# Schieberegister_Tr_gerplatine.net
KiCad netlist of a schematic drawn in Altium Designer
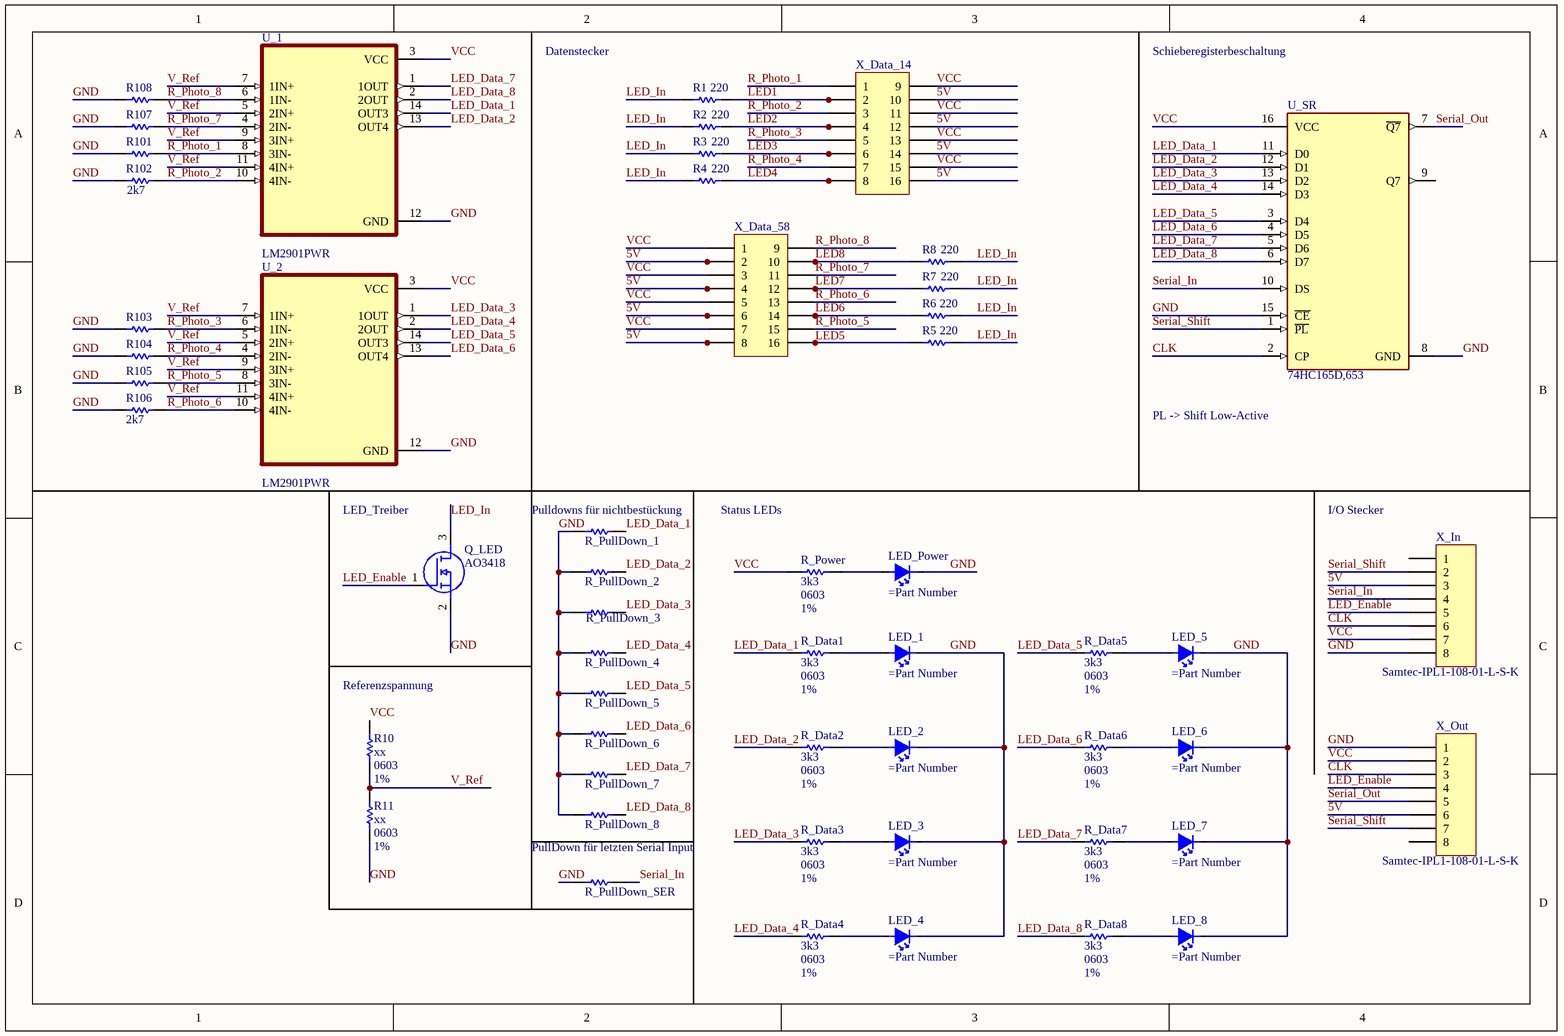
[diagram p0: Schieberegister_Trägerplatine.SchDoc]

(export (version "E")
  (design (tool "Eeschema 10.0.6"))
  (components
    (comp (ref "LED_1")
      (value "~")
      (footprint "150060XX75000")
      (fields (field (name "PART NUMBER") "150060*75000") (field (name "MANUFACTURER") "Würth"))
      (libsource (lib "FSE_Library_nora7") (part "LED_0603"))
    )
    (comp (ref "LED_2")
      (value "~")
      (footprint "150060XX75000")
      (fields (field (name "PART NUMBER") "150060*75000") (field (name "MANUFACTURER") "Würth"))
      (libsource (lib "FSE_Library_nora7") (part "LED_0603"))
    )
    (comp (ref "LED_3")
      (value "~")
      (footprint "150060XX75000")
      (fields (field (name "PART NUMBER") "150060*75000") (field (name "MANUFACTURER") "Würth"))
      (libsource (lib "FSE_Library_nora7") (part "LED_0603"))
    )
    (comp (ref "LED_4")
      (value "~")
      (footprint "150060XX75000")
      (fields (field (name "PART NUMBER") "150060*75000") (field (name "MANUFACTURER") "Würth"))
      (libsource (lib "FSE_Library_nora7") (part "LED_0603"))
    )
    (comp (ref "LED_5")
      (value "~")
      (footprint "150060XX75000")
      (fields (field (name "PART NUMBER") "150060*75000") (field (name "MANUFACTURER") "Würth"))
      (libsource (lib "FSE_Library_nora7") (part "LED_0603"))
    )
    (comp (ref "LED_6")
      (value "~")
      (footprint "150060XX75000")
      (fields (field (name "PART NUMBER") "150060*75000") (field (name "MANUFACTURER") "Würth"))
      (libsource (lib "FSE_Library_nora7") (part "LED_0603"))
    )
    (comp (ref "LED_7")
      (value "~")
      (footprint "150060XX75000")
      (fields (field (name "PART NUMBER") "150060*75000") (field (name "MANUFACTURER") "Würth"))
      (libsource (lib "FSE_Library_nora7") (part "LED_0603"))
    )
    (comp (ref "LED_8")
      (value "~")
      (footprint "150060XX75000")
      (fields (field (name "PART NUMBER") "150060*75000") (field (name "MANUFACTURER") "Würth"))
      (libsource (lib "FSE_Library_nora7") (part "LED_0603"))
    )
    (comp (ref "LED_Power")
      (value "~")
      (footprint "150060XX75000")
      (fields (field (name "PART NUMBER") "150060*75000") (field (name "MANUFACTURER") "Würth"))
      (libsource (lib "FSE_Library_nora7") (part "LED_0603"))
    )
    (comp (ref "Q_LED")
      (value "AO3418")
      (footprint "SOT95P280X125-3N")
      (description "MOSFET N-CH 30V 3.8A SOT23")
      (libsource (lib "AO3418") (part "AO3418"))
    )
    (comp (ref "R1")
      (value "220")
      (footprint "FSE_Library_nora7:0603_resistor_flat")
      (description "Resistor, 0603, 5% default, 0.1 W")
      (fields (field (name "PART NUMBER") "R___220"))
      (libsource (lib "FSE_Library_nora7") (part "R_0603"))
    )
    (comp (ref "R2")
      (value "220")
      (footprint "FSE_Library_nora7:0603_resistor_flat")
      (description "Resistor, 0603, 5% default, 0.1 W")
      (fields (field (name "PART NUMBER") "R___220"))
      (libsource (lib "FSE_Library_nora7") (part "R_0603"))
    )
    (comp (ref "R3")
      (value "220")
      (footprint "FSE_Library_nora7:0603_resistor_flat")
      (description "Resistor, 0603, 5% default, 0.1 W")
      (fields (field (name "PART NUMBER") "R___220"))
      (libsource (lib "FSE_Library_nora7") (part "R_0603"))
    )
    (comp (ref "R4")
      (value "220")
      (footprint "FSE_Library_nora7:0603_resistor_flat")
      (description "Resistor, 0603, 5% default, 0.1 W")
      (fields (field (name "PART NUMBER") "R___220"))
      (libsource (lib "FSE_Library_nora7") (part "R_0603"))
    )
    (comp (ref "R5")
      (value "220")
      (footprint "FSE_Library_nora7:0603_resistor_flat")
      (description "Resistor, 0603, 5% default, 0.1 W")
      (fields (field (name "PART NUMBER") "R___220"))
      (libsource (lib "FSE_Library_nora7") (part "R_0603"))
    )
    (comp (ref "R6")
      (value "220")
      (footprint "FSE_Library_nora7:0603_resistor_flat")
      (description "Resistor, 0603, 5% default, 0.1 W")
      (fields (field (name "PART NUMBER") "R___220"))
      (libsource (lib "FSE_Library_nora7") (part "R_0603"))
    )
    (comp (ref "R7")
      (value "220")
      (footprint "FSE_Library_nora7:0603_resistor_flat")
      (description "Resistor, 0603, 5% default, 0.1 W")
      (fields (field (name "PART NUMBER") "R___220"))
      (libsource (lib "FSE_Library_nora7") (part "R_0603"))
    )
    (comp (ref "R8")
      (value "220")
      (footprint "FSE_Library_nora7:0603_resistor_flat")
      (description "Resistor, 0603, 5% default, 0.1 W")
      (fields (field (name "PART NUMBER") "R___220"))
      (libsource (lib "FSE_Library_nora7") (part "R_0603"))
    )
    (comp (ref "R10")
      (value "xx")
      (footprint "FSE_Library_nora7:0603_resistor_flat")
      (description "Resistor, 0603, 5% default, 0.1 W")
      (fields
        (field (name "PART NUMBER") "R_0603_1%_xx")
        (field (name "CASE_EIA") "0603")
        (field (name "TOLERANCE") "1%")
      )
      (libsource (lib "FSE_Library_nora7") (part "R_0603"))
    )
    (comp (ref "R11")
      (value "xx")
      (footprint "FSE_Library_nora7:0603_resistor_flat")
      (description "Resistor, 0603, 5% default, 0.1 W")
      (fields
        (field (name "PART NUMBER") "R_0603_1%_xx")
        (field (name "CASE_EIA") "0603")
        (field (name "TOLERANCE") "1%")
      )
      (libsource (lib "FSE_Library_nora7") (part "R_0603"))
    )
    (comp (ref "R101")
      (value "~")
      (footprint "FSE_Library_nora7:0603_resistor_flat")
      (description "Resistor, 0603, 5% default, 0.1 W")
      (fields (field (name "PART NUMBER") "R___"))
      (libsource (lib "FSE_Library_nora7") (part "R_0603"))
    )
    (comp (ref "R102")
      (value "2k7")
      (footprint "FSE_Library_nora7:0603_resistor_flat")
      (description "Resistor, 0603, 5% default, 0.1 W")
      (fields (field (name "PART NUMBER") "R___"))
      (libsource (lib "FSE_Library_nora7") (part "R_0603"))
    )
    (comp (ref "R103")
      (value "~")
      (footprint "FSE_Library_nora7:0603_resistor_flat")
      (description "Resistor, 0603, 5% default, 0.1 W")
      (fields (field (name "PART NUMBER") "R___"))
      (libsource (lib "FSE_Library_nora7") (part "R_0603"))
    )
    (comp (ref "R104")
      (value "~")
      (footprint "FSE_Library_nora7:0603_resistor_flat")
      (description "Resistor, 0603, 5% default, 0.1 W")
      (fields (field (name "PART NUMBER") "R___"))
      (libsource (lib "FSE_Library_nora7") (part "R_0603"))
    )
    (comp (ref "R105")
      (value "~")
      (footprint "FSE_Library_nora7:0603_resistor_flat")
      (description "Resistor, 0603, 5% default, 0.1 W")
      (fields (field (name "PART NUMBER") "R___"))
      (libsource (lib "FSE_Library_nora7") (part "R_0603"))
    )
    (comp (ref "R106")
      (value "2k7")
      (footprint "FSE_Library_nora7:0603_resistor_flat")
      (description "Resistor, 0603, 5% default, 0.1 W")
      (fields (field (name "PART NUMBER") "R___"))
      (libsource (lib "FSE_Library_nora7") (part "R_0603"))
    )
    (comp (ref "R107")
      (value "~")
      (footprint "FSE_Library_nora7:0603_resistor_flat")
      (description "Resistor, 0603, 5% default, 0.1 W")
      (fields (field (name "PART NUMBER") "R___"))
      (libsource (lib "FSE_Library_nora7") (part "R_0603"))
    )
    (comp (ref "R108")
      (value "~")
      (footprint "FSE_Library_nora7:0603_resistor_flat")
      (description "Resistor, 0603, 5% default, 0.1 W")
      (fields (field (name "PART NUMBER") "R___"))
      (libsource (lib "FSE_Library_nora7") (part "R_0603"))
    )
    (comp (ref "R_Data1")
      (value "3k3")
      (footprint "FSE_Library_nora7:0603_resistor_flat")
      (description "Resistor, 0603, 5% default, 0.1 W")
      (fields
        (field (name "PART NUMBER") "R_0603_1%_3k3")
        (field (name "CASE_EIA") "0603")
        (field (name "TOLERANCE") "1%")
      )
      (libsource (lib "FSE_Library_nora7") (part "R_0603"))
    )
    (comp (ref "R_Data2")
      (value "3k3")
      (footprint "FSE_Library_nora7:0603_resistor_flat")
      (description "Resistor, 0603, 5% default, 0.1 W")
      (fields
        (field (name "PART NUMBER") "R_0603_1%_3k3")
        (field (name "CASE_EIA") "0603")
        (field (name "TOLERANCE") "1%")
      )
      (libsource (lib "FSE_Library_nora7") (part "R_0603"))
    )
    (comp (ref "R_Data3")
      (value "3k3")
      (footprint "FSE_Library_nora7:0603_resistor_flat")
      (description "Resistor, 0603, 5% default, 0.1 W")
      (fields
        (field (name "PART NUMBER") "R_0603_1%_3k3")
        (field (name "CASE_EIA") "0603")
        (field (name "TOLERANCE") "1%")
      )
      (libsource (lib "FSE_Library_nora7") (part "R_0603"))
    )
    (comp (ref "R_Data4")
      (value "3k3")
      (footprint "FSE_Library_nora7:0603_resistor_flat")
      (description "Resistor, 0603, 5% default, 0.1 W")
      (fields
        (field (name "PART NUMBER") "R_0603_1%_3k3")
        (field (name "CASE_EIA") "0603")
        (field (name "TOLERANCE") "1%")
      )
      (libsource (lib "FSE_Library_nora7") (part "R_0603"))
    )
    (comp (ref "R_Data5")
      (value "3k3")
      (footprint "FSE_Library_nora7:0603_resistor_flat")
      (description "Resistor, 0603, 5% default, 0.1 W")
      (fields
        (field (name "PART NUMBER") "R_0603_1%_3k3")
        (field (name "CASE_EIA") "0603")
        (field (name "TOLERANCE") "1%")
      )
      (libsource (lib "FSE_Library_nora7") (part "R_0603"))
    )
    (comp (ref "R_Data6")
      (value "3k3")
      (footprint "FSE_Library_nora7:0603_resistor_flat")
      (description "Resistor, 0603, 5% default, 0.1 W")
      (fields
        (field (name "PART NUMBER") "R_0603_1%_3k3")
        (field (name "CASE_EIA") "0603")
        (field (name "TOLERANCE") "1%")
      )
      (libsource (lib "FSE_Library_nora7") (part "R_0603"))
    )
    (comp (ref "R_Data7")
      (value "3k3")
      (footprint "FSE_Library_nora7:0603_resistor_flat")
      (description "Resistor, 0603, 5% default, 0.1 W")
      (fields
        (field (name "PART NUMBER") "R_0603_1%_3k3")
        (field (name "CASE_EIA") "0603")
        (field (name "TOLERANCE") "1%")
      )
      (libsource (lib "FSE_Library_nora7") (part "R_0603"))
    )
    (comp (ref "R_Data8")
      (value "3k3")
      (footprint "FSE_Library_nora7:0603_resistor_flat")
      (description "Resistor, 0603, 5% default, 0.1 W")
      (fields
        (field (name "PART NUMBER") "R_0603_1%_3k3")
        (field (name "CASE_EIA") "0603")
        (field (name "TOLERANCE") "1%")
      )
      (libsource (lib "FSE_Library_nora7") (part "R_0603"))
    )
    (comp (ref "R_Power")
      (value "3k3")
      (footprint "FSE_Library_nora7:0603_resistor_flat")
      (description "Resistor, 0603, 5% default, 0.1 W")
      (fields
        (field (name "PART NUMBER") "R_0603_1%_3k3")
        (field (name "CASE_EIA") "0603")
        (field (name "TOLERANCE") "1%")
      )
      (libsource (lib "FSE_Library_nora7") (part "R_0603"))
    )
    (comp (ref "R_PullDown_1")
      (value "~")
      (footprint "FSE_Library_nora7:0603_resistor_flat")
      (description "Resistor, 0603, 5% default, 0.1 W")
      (fields (field (name "PART NUMBER") "R___"))
      (libsource (lib "FSE_Library_nora7") (part "R_0603"))
    )
    (comp (ref "R_PullDown_2")
      (value "~")
      (footprint "FSE_Library_nora7:0603_resistor_flat")
      (description "Resistor, 0603, 5% default, 0.1 W")
      (fields (field (name "PART NUMBER") "R___"))
      (libsource (lib "FSE_Library_nora7") (part "R_0603"))
    )
    (comp (ref "R_PullDown_3")
      (value "~")
      (footprint "FSE_Library_nora7:0603_resistor_flat")
      (description "Resistor, 0603, 5% default, 0.1 W")
      (fields (field (name "PART NUMBER") "R___"))
      (libsource (lib "FSE_Library_nora7") (part "R_0603"))
    )
    (comp (ref "R_PullDown_4")
      (value "~")
      (footprint "FSE_Library_nora7:0603_resistor_flat")
      (description "Resistor, 0603, 5% default, 0.1 W")
      (fields (field (name "PART NUMBER") "R___"))
      (libsource (lib "FSE_Library_nora7") (part "R_0603"))
    )
    (comp (ref "R_PullDown_5")
      (value "~")
      (footprint "FSE_Library_nora7:0603_resistor_flat")
      (description "Resistor, 0603, 5% default, 0.1 W")
      (fields (field (name "PART NUMBER") "R___"))
      (libsource (lib "FSE_Library_nora7") (part "R_0603"))
    )
    (comp (ref "R_PullDown_6")
      (value "~")
      (footprint "FSE_Library_nora7:0603_resistor_flat")
      (description "Resistor, 0603, 5% default, 0.1 W")
      (fields (field (name "PART NUMBER") "R___"))
      (libsource (lib "FSE_Library_nora7") (part "R_0603"))
    )
    (comp (ref "R_PullDown_7")
      (value "~")
      (footprint "FSE_Library_nora7:0603_resistor_flat")
      (description "Resistor, 0603, 5% default, 0.1 W")
      (fields (field (name "PART NUMBER") "R___"))
      (libsource (lib "FSE_Library_nora7") (part "R_0603"))
    )
    (comp (ref "R_PullDown_8")
      (value "~")
      (footprint "FSE_Library_nora7:0603_resistor_flat")
      (description "Resistor, 0603, 5% default, 0.1 W")
      (fields (field (name "PART NUMBER") "R___"))
      (libsource (lib "FSE_Library_nora7") (part "R_0603"))
    )
    (comp (ref "R_PullDown_SER")
      (value "~")
      (footprint "FSE_Library_nora7:0603_resistor_flat")
      (description "Resistor, 0603, 5% default, 0.1 W")
      (fields (field (name "PART NUMBER") "R___"))
      (libsource (lib "FSE_Library_nora7") (part "R_0603"))
    )
    (comp (ref "U_1")
      (value "LM2901PWR")
      (footprint "SOP65P640X120-14N")
      (description "Quad differential comparator, automotive grade 14-TSSOP -40 to 125")
      (fields (field (name "MF") "Texas"))
      (libsource (lib "LM2901PWR") (part "LM2901PWR"))
    )
    (comp (ref "U_2")
      (value "LM2901PWR")
      (footprint "SOP65P640X120-14N")
      (description "Quad differential comparator, automotive grade 14-TSSOP -40 to 125")
      (fields (field (name "MF") "Texas"))
      (libsource (lib "LM2901PWR") (part "LM2901PWR"))
    )
    (comp (ref "U_SR")
      (value "74HC165D,653")
      (footprint "FP-SOT109-1-MFG")
      (description "IC SHIFT REGST 8BIT PI-SO 16SOIC")
      (fields
        (field (name "MANUFACTURER") "Nexperia")
        (field (name "OCTOPART") "https://octopart.com/74hc165d%2C653-nexperia-78737091")
      )
      (libsource (lib "Altium Content Vault") (part "62206be407dde36a55674a9f8997e2d"))
    )
    (comp (ref "X_Data_14")
      (value "Samtec-IPL1-108-01-L-D-K")
      (footprint "Samtec-IPL1-108-01-L-D-K")
      (description "Header, 8-Pin, Dual row")
      (fields (field (name "PUBLISHER") "Altium Limited"))
      (libsource (lib "FSE_Library_connector") (part "Samtec-IPL1-108-01-L-D-K"))
    )
    (comp (ref "X_Data_58")
      (value "Samtec-IPL1-108-01-L-D-K")
      (footprint "Samtec-IPL1-108-01-L-D-K")
      (description "Header, 8-Pin, Dual row")
      (fields (field (name "PUBLISHER") "Altium Limited"))
      (libsource (lib "FSE_Library_connector") (part "Samtec-IPL1-108-01-L-D-K"))
    )
    (comp (ref "X_In")
      (value "Samtec-IPL1-108-01-L-S-K")
      (footprint "Samtec-IPL1-108-01-L-S-K")
      (description "Header, 8-Pin")
      (fields (field (name "PUBLISHER") "Altium Limited"))
      (libsource (lib "FSE_Library_connector") (part "IPL1-108-01-L-S-K"))
    )
    (comp (ref "X_Out")
      (value "Samtec-IPL1-108-01-L-S-K")
      (footprint "Samtec-IPL1-108-01-L-S-K")
      (description "Header, 8-Pin")
      (fields (field (name "PUBLISHER") "Altium Limited"))
      (libsource (lib "FSE_Library_connector") (part "IPL1-108-01-L-S-K"))
    )
  )
  (nets
    (net (code "1") (name "/5V") (class "Default")
      (node (ref "X_Data_14") (pin "10") (pinfunction "10_10") (pintype "passive"))
      (node (ref "X_Data_14") (pin "12") (pinfunction "12_12") (pintype "passive"))
      (node (ref "X_Data_14") (pin "14") (pinfunction "14_14") (pintype "passive"))
      (node (ref "X_Data_14") (pin "16") (pinfunction "16_16") (pintype "passive"))
      (node (ref "X_Data_58") (pin "2") (pinfunction "2_2") (pintype "passive"))
      (node (ref "X_Data_58") (pin "4") (pinfunction "4_4") (pintype "passive"))
      (node (ref "X_Data_58") (pin "6") (pinfunction "6_6") (pintype "passive"))
      (node (ref "X_Data_58") (pin "8") (pinfunction "8_8") (pintype "passive"))
      (node (ref "X_In") (pin "3") (pinfunction "3_3") (pintype "passive"))
      (node (ref "X_Out") (pin "6") (pinfunction "6_6") (pintype "passive"))
    )
    (net (code "2") (name "/CLK") (class "Default")
      (node (ref "U_SR") (pin "2") (pinfunction "CP_2") (pintype "input"))
      (node (ref "X_In") (pin "6") (pinfunction "6_6") (pintype "passive"))
      (node (ref "X_Out") (pin "3") (pinfunction "3_3") (pintype "passive"))
    )
    (net (code "3") (name "/GND") (class "Default")
      (node (ref "LED_1") (pin "1") (pinfunction "Cathode_1") (pintype "passive"))
      (node (ref "LED_2") (pin "1") (pinfunction "Cathode_1") (pintype "passive"))
      (node (ref "LED_3") (pin "1") (pinfunction "Cathode_1") (pintype "passive"))
      (node (ref "LED_4") (pin "1") (pinfunction "Cathode_1") (pintype "passive"))
      (node (ref "LED_5") (pin "1") (pinfunction "Cathode_1") (pintype "passive"))
      (node (ref "LED_6") (pin "1") (pinfunction "Cathode_1") (pintype "passive"))
      (node (ref "LED_7") (pin "1") (pinfunction "Cathode_1") (pintype "passive"))
      (node (ref "LED_8") (pin "1") (pinfunction "Cathode_1") (pintype "passive"))
      (node (ref "LED_Power") (pin "1") (pinfunction "Cathode_1") (pintype "passive"))
      (node (ref "Q_LED") (pin "2") (pinfunction "S_2") (pintype "passive"))
      (node (ref "R101") (pin "1") (pinfunction "1_1") (pintype "passive"))
      (node (ref "R102") (pin "1") (pinfunction "1_1") (pintype "passive"))
      (node (ref "R103") (pin "1") (pinfunction "1_1") (pintype "passive"))
      (node (ref "R104") (pin "1") (pinfunction "1_1") (pintype "passive"))
      (node (ref "R105") (pin "1") (pinfunction "1_1") (pintype "passive"))
      (node (ref "R106") (pin "1") (pinfunction "1_1") (pintype "passive"))
      (node (ref "R107") (pin "1") (pinfunction "1_1") (pintype "passive"))
      (node (ref "R108") (pin "1") (pinfunction "1_1") (pintype "passive"))
      (node (ref "R11") (pin "1") (pinfunction "1_1") (pintype "passive"))
      (node (ref "R_PullDown_1") (pin "1") (pinfunction "1_1") (pintype "passive"))
      (node (ref "R_PullDown_2") (pin "1") (pinfunction "1_1") (pintype "passive"))
      (node (ref "R_PullDown_3") (pin "1") (pinfunction "1_1") (pintype "passive"))
      (node (ref "R_PullDown_4") (pin "1") (pinfunction "1_1") (pintype "passive"))
      (node (ref "R_PullDown_5") (pin "1") (pinfunction "1_1") (pintype "passive"))
      (node (ref "R_PullDown_6") (pin "1") (pinfunction "1_1") (pintype "passive"))
      (node (ref "R_PullDown_7") (pin "1") (pinfunction "1_1") (pintype "passive"))
      (node (ref "R_PullDown_8") (pin "1") (pinfunction "1_1") (pintype "passive"))
      (node (ref "R_PullDown_SER") (pin "1") (pinfunction "1_1") (pintype "passive"))
      (node (ref "U_1") (pin "12") (pinfunction "GND_12") (pintype "power_in"))
      (node (ref "U_2") (pin "12") (pinfunction "GND_12") (pintype "power_in"))
      (node (ref "U_SR") (pin "15") (pinfunction "~{CE}_15") (pintype "input"))
      (node (ref "U_SR") (pin "8") (pinfunction "GND_8") (pintype "power_in"))
      (node (ref "X_In") (pin "8") (pinfunction "8_8") (pintype "passive"))
      (node (ref "X_Out") (pin "1") (pinfunction "1_1") (pintype "passive"))
    )
    (net (code "4") (name "/LED1") (class "Default")
      (node (ref "R1") (pin "1") (pinfunction "1_1") (pintype "passive"))
      (node (ref "X_Data_14") (pin "2") (pinfunction "2_2") (pintype "passive"))
    )
    (net (code "5") (name "/LED2") (class "Default")
      (node (ref "R2") (pin "1") (pinfunction "1_1") (pintype "passive"))
      (node (ref "X_Data_14") (pin "4") (pinfunction "4_4") (pintype "passive"))
    )
    (net (code "6") (name "/LED3") (class "Default")
      (node (ref "R3") (pin "1") (pinfunction "1_1") (pintype "passive"))
      (node (ref "X_Data_14") (pin "6") (pinfunction "6_6") (pintype "passive"))
    )
    (net (code "7") (name "/LED4") (class "Default")
      (node (ref "R4") (pin "1") (pinfunction "1_1") (pintype "passive"))
      (node (ref "X_Data_14") (pin "8") (pinfunction "8_8") (pintype "passive"))
    )
    (net (code "8") (name "/LED5") (class "Default")
      (node (ref "R5") (pin "1") (pinfunction "1_1") (pintype "passive"))
      (node (ref "X_Data_58") (pin "16") (pinfunction "16_16") (pintype "passive"))
    )
    (net (code "9") (name "/LED6") (class "Default")
      (node (ref "R6") (pin "1") (pinfunction "1_1") (pintype "passive"))
      (node (ref "X_Data_58") (pin "14") (pinfunction "14_14") (pintype "passive"))
    )
    (net (code "10") (name "/LED7") (class "Default")
      (node (ref "R7") (pin "1") (pinfunction "1_1") (pintype "passive"))
      (node (ref "X_Data_58") (pin "12") (pinfunction "12_12") (pintype "passive"))
    )
    (net (code "11") (name "/LED8") (class "Default")
      (node (ref "R8") (pin "1") (pinfunction "1_1") (pintype "passive"))
      (node (ref "X_Data_58") (pin "10") (pinfunction "10_10") (pintype "passive"))
    )
    (net (code "12") (name "/LED_Data_1") (class "Default")
      (node (ref "R_Data1") (pin "2") (pinfunction "2_2") (pintype "passive"))
      (node (ref "R_PullDown_1") (pin "2") (pinfunction "2_2") (pintype "passive"))
      (node (ref "U_1") (pin "14") (pinfunction "OUT3_14") (pintype "output"))
      (node (ref "U_SR") (pin "11") (pinfunction "D0_11") (pintype "input"))
    )
    (net (code "13") (name "/LED_Data_2") (class "Default")
      (node (ref "R_Data2") (pin "2") (pinfunction "2_2") (pintype "passive"))
      (node (ref "R_PullDown_2") (pin "2") (pinfunction "2_2") (pintype "passive"))
      (node (ref "U_1") (pin "13") (pinfunction "OUT4_13") (pintype "output"))
      (node (ref "U_SR") (pin "12") (pinfunction "D1_12") (pintype "input"))
    )
    (net (code "14") (name "/LED_Data_3") (class "Default")
      (node (ref "R_Data3") (pin "2") (pinfunction "2_2") (pintype "passive"))
      (node (ref "R_PullDown_3") (pin "2") (pinfunction "2_2") (pintype "passive"))
      (node (ref "U_2") (pin "1") (pinfunction "1OUT_1") (pintype "output"))
      (node (ref "U_SR") (pin "13") (pinfunction "D2_13") (pintype "input"))
    )
    (net (code "15") (name "/LED_Data_4") (class "Default")
      (node (ref "R_Data4") (pin "2") (pinfunction "2_2") (pintype "passive"))
      (node (ref "R_PullDown_4") (pin "2") (pinfunction "2_2") (pintype "passive"))
      (node (ref "U_2") (pin "2") (pinfunction "2OUT_2") (pintype "output"))
      (node (ref "U_SR") (pin "14") (pinfunction "D3_14") (pintype "input"))
    )
    (net (code "16") (name "/LED_Data_5") (class "Default")
      (node (ref "R_Data5") (pin "2") (pinfunction "2_2") (pintype "passive"))
      (node (ref "R_PullDown_5") (pin "2") (pinfunction "2_2") (pintype "passive"))
      (node (ref "U_2") (pin "14") (pinfunction "OUT3_14") (pintype "output"))
      (node (ref "U_SR") (pin "3") (pinfunction "D4_3") (pintype "input"))
    )
    (net (code "17") (name "/LED_Data_6") (class "Default")
      (node (ref "R_Data6") (pin "2") (pinfunction "2_2") (pintype "passive"))
      (node (ref "R_PullDown_6") (pin "2") (pinfunction "2_2") (pintype "passive"))
      (node (ref "U_2") (pin "13") (pinfunction "OUT4_13") (pintype "output"))
      (node (ref "U_SR") (pin "4") (pinfunction "D5_4") (pintype "input"))
    )
    (net (code "18") (name "/LED_Data_7") (class "Default")
      (node (ref "R_Data7") (pin "2") (pinfunction "2_2") (pintype "passive"))
      (node (ref "R_PullDown_7") (pin "2") (pinfunction "2_2") (pintype "passive"))
      (node (ref "U_1") (pin "1") (pinfunction "1OUT_1") (pintype "output"))
      (node (ref "U_SR") (pin "5") (pinfunction "D6_5") (pintype "input"))
    )
    (net (code "19") (name "/LED_Data_8") (class "Default")
      (node (ref "R_Data8") (pin "2") (pinfunction "2_2") (pintype "passive"))
      (node (ref "R_PullDown_8") (pin "2") (pinfunction "2_2") (pintype "passive"))
      (node (ref "U_1") (pin "2") (pinfunction "2OUT_2") (pintype "output"))
      (node (ref "U_SR") (pin "6") (pinfunction "D7_6") (pintype "input"))
    )
    (net (code "20") (name "/LED_Enable") (class "Default")
      (node (ref "Q_LED") (pin "1") (pinfunction "G_1") (pintype "passive"))
      (node (ref "X_In") (pin "5") (pinfunction "5_5") (pintype "passive"))
      (node (ref "X_Out") (pin "4") (pinfunction "4_4") (pintype "passive"))
    )
    (net (code "21") (name "/LED_In") (class "Default")
      (node (ref "Q_LED") (pin "3") (pinfunction "D_3") (pintype "passive"))
      (node (ref "R1") (pin "2") (pinfunction "2_2") (pintype "passive"))
      (node (ref "R2") (pin "2") (pinfunction "2_2") (pintype "passive"))
      (node (ref "R3") (pin "2") (pinfunction "2_2") (pintype "passive"))
      (node (ref "R4") (pin "2") (pinfunction "2_2") (pintype "passive"))
      (node (ref "R5") (pin "2") (pinfunction "2_2") (pintype "passive"))
      (node (ref "R6") (pin "2") (pinfunction "2_2") (pintype "passive"))
      (node (ref "R7") (pin "2") (pinfunction "2_2") (pintype "passive"))
      (node (ref "R8") (pin "2") (pinfunction "2_2") (pintype "passive"))
    )
    (net (code "22") (name "/R_Photo_1") (class "Default")
      (node (ref "R101") (pin "2") (pinfunction "2_2") (pintype "passive"))
      (node (ref "U_1") (pin "8") (pinfunction "3IN-_8") (pintype "input"))
      (node (ref "X_Data_14") (pin "1") (pinfunction "1_1") (pintype "passive"))
    )
    (net (code "23") (name "/R_Photo_2") (class "Default")
      (node (ref "R102") (pin "2") (pinfunction "2_2") (pintype "passive"))
      (node (ref "U_1") (pin "10") (pinfunction "4IN-_10") (pintype "input"))
      (node (ref "X_Data_14") (pin "3") (pinfunction "3_3") (pintype "passive"))
    )
    (net (code "24") (name "/R_Photo_3") (class "Default")
      (node (ref "R103") (pin "2") (pinfunction "2_2") (pintype "passive"))
      (node (ref "U_2") (pin "6") (pinfunction "1IN-_6") (pintype "input"))
      (node (ref "X_Data_14") (pin "5") (pinfunction "5_5") (pintype "passive"))
    )
    (net (code "25") (name "/R_Photo_4") (class "Default")
      (node (ref "R104") (pin "2") (pinfunction "2_2") (pintype "passive"))
      (node (ref "U_2") (pin "4") (pinfunction "2IN-_4") (pintype "input"))
      (node (ref "X_Data_14") (pin "7") (pinfunction "7_7") (pintype "passive"))
    )
    (net (code "26") (name "/R_Photo_5") (class "Default")
      (node (ref "R105") (pin "2") (pinfunction "2_2") (pintype "passive"))
      (node (ref "U_2") (pin "8") (pinfunction "3IN-_8") (pintype "input"))
      (node (ref "X_Data_58") (pin "15") (pinfunction "15_15") (pintype "passive"))
    )
    (net (code "27") (name "/R_Photo_6") (class "Default")
      (node (ref "R106") (pin "2") (pinfunction "2_2") (pintype "passive"))
      (node (ref "U_2") (pin "10") (pinfunction "4IN-_10") (pintype "input"))
      (node (ref "X_Data_58") (pin "13") (pinfunction "13_13") (pintype "passive"))
    )
    (net (code "28") (name "/R_Photo_7") (class "Default")
      (node (ref "R107") (pin "2") (pinfunction "2_2") (pintype "passive"))
      (node (ref "U_1") (pin "4") (pinfunction "2IN-_4") (pintype "input"))
      (node (ref "X_Data_58") (pin "11") (pinfunction "11_11") (pintype "passive"))
    )
    (net (code "29") (name "/R_Photo_8") (class "Default")
      (node (ref "R108") (pin "2") (pinfunction "2_2") (pintype "passive"))
      (node (ref "U_1") (pin "6") (pinfunction "1IN-_6") (pintype "input"))
      (node (ref "X_Data_58") (pin "9") (pinfunction "9_9") (pintype "passive"))
    )
    (net (code "30") (name "/Serial_In") (class "Default")
      (node (ref "R_PullDown_SER") (pin "2") (pinfunction "2_2") (pintype "passive"))
      (node (ref "U_SR") (pin "10") (pinfunction "DS_10") (pintype "input"))
      (node (ref "X_In") (pin "4") (pinfunction "4_4") (pintype "passive"))
    )
    (net (code "31") (name "/Serial_Out") (class "Default")
      (node (ref "U_SR") (pin "7") (pinfunction "~{Q7}_7") (pintype "output"))
      (node (ref "X_Out") (pin "5") (pinfunction "5_5") (pintype "passive"))
    )
    (net (code "32") (name "/Serial_Shift") (class "Default")
      (node (ref "U_SR") (pin "1") (pinfunction "~{PL}_1") (pintype "input"))
      (node (ref "X_In") (pin "2") (pinfunction "2_2") (pintype "passive"))
      (node (ref "X_Out") (pin "7") (pinfunction "7_7") (pintype "passive"))
    )
    (net (code "33") (name "/VCC") (class "Default")
      (node (ref "R10") (pin "2") (pinfunction "2_2") (pintype "passive"))
      (node (ref "R_Power") (pin "2") (pinfunction "2_2") (pintype "passive"))
      (node (ref "U_1") (pin "3") (pinfunction "VCC_3") (pintype "power_in"))
      (node (ref "U_2") (pin "3") (pinfunction "VCC_3") (pintype "power_in"))
      (node (ref "U_SR") (pin "16") (pinfunction "VCC_16") (pintype "power_in"))
      (node (ref "X_Data_14") (pin "11") (pinfunction "11_11") (pintype "passive"))
      (node (ref "X_Data_14") (pin "13") (pinfunction "13_13") (pintype "passive"))
      (node (ref "X_Data_14") (pin "15") (pinfunction "15_15") (pintype "passive"))
      (node (ref "X_Data_14") (pin "9") (pinfunction "9_9") (pintype "passive"))
      (node (ref "X_Data_58") (pin "1") (pinfunction "1_1") (pintype "passive"))
      (node (ref "X_Data_58") (pin "3") (pinfunction "3_3") (pintype "passive"))
      (node (ref "X_Data_58") (pin "5") (pinfunction "5_5") (pintype "passive"))
      (node (ref "X_Data_58") (pin "7") (pinfunction "7_7") (pintype "passive"))
      (node (ref "X_In") (pin "7") (pinfunction "7_7") (pintype "passive"))
      (node (ref "X_Out") (pin "2") (pinfunction "2_2") (pintype "passive"))
    )
    (net (code "34") (name "/V_Ref") (class "Default")
      (node (ref "R10") (pin "1") (pinfunction "1_1") (pintype "passive"))
      (node (ref "R11") (pin "2") (pinfunction "2_2") (pintype "passive"))
      (node (ref "U_1") (pin "11") (pinfunction "4IN+_11") (pintype "input"))
      (node (ref "U_1") (pin "5") (pinfunction "2IN+_5") (pintype "input"))
      (node (ref "U_1") (pin "7") (pinfunction "1IN+_7") (pintype "input"))
      (node (ref "U_1") (pin "9") (pinfunction "3IN+_9") (pintype "input"))
      (node (ref "U_2") (pin "11") (pinfunction "4IN+_11") (pintype "input"))
      (node (ref "U_2") (pin "5") (pinfunction "2IN+_5") (pintype "input"))
      (node (ref "U_2") (pin "7") (pinfunction "1IN+_7") (pintype "input"))
      (node (ref "U_2") (pin "9") (pinfunction "3IN+_9") (pintype "input"))
    )
    (net (code "35") (name "Net-(LED_1-Anode)") (class "Default")
      (node (ref "LED_1") (pin "2") (pinfunction "Anode_2") (pintype "passive"))
      (node (ref "R_Data1") (pin "1") (pinfunction "1_1") (pintype "passive"))
    )
    (net (code "36") (name "Net-(LED_2-Anode)") (class "Default")
      (node (ref "LED_2") (pin "2") (pinfunction "Anode_2") (pintype "passive"))
      (node (ref "R_Data2") (pin "1") (pinfunction "1_1") (pintype "passive"))
    )
    (net (code "37") (name "Net-(LED_3-Anode)") (class "Default")
      (node (ref "LED_3") (pin "2") (pinfunction "Anode_2") (pintype "passive"))
      (node (ref "R_Data3") (pin "1") (pinfunction "1_1") (pintype "passive"))
    )
    (net (code "38") (name "Net-(LED_4-Anode)") (class "Default")
      (node (ref "LED_4") (pin "2") (pinfunction "Anode_2") (pintype "passive"))
      (node (ref "R_Data4") (pin "1") (pinfunction "1_1") (pintype "passive"))
    )
    (net (code "39") (name "Net-(LED_5-Anode)") (class "Default")
      (node (ref "LED_5") (pin "2") (pinfunction "Anode_2") (pintype "passive"))
      (node (ref "R_Data5") (pin "1") (pinfunction "1_1") (pintype "passive"))
    )
    (net (code "40") (name "Net-(LED_6-Anode)") (class "Default")
      (node (ref "LED_6") (pin "2") (pinfunction "Anode_2") (pintype "passive"))
      (node (ref "R_Data6") (pin "1") (pinfunction "1_1") (pintype "passive"))
    )
    (net (code "41") (name "Net-(LED_7-Anode)") (class "Default")
      (node (ref "LED_7") (pin "2") (pinfunction "Anode_2") (pintype "passive"))
      (node (ref "R_Data7") (pin "1") (pinfunction "1_1") (pintype "passive"))
    )
    (net (code "42") (name "Net-(LED_8-Anode)") (class "Default")
      (node (ref "LED_8") (pin "2") (pinfunction "Anode_2") (pintype "passive"))
      (node (ref "R_Data8") (pin "1") (pinfunction "1_1") (pintype "passive"))
    )
    (net (code "43") (name "Net-(LED_Power-Anode)") (class "Default")
      (node (ref "LED_Power") (pin "2") (pinfunction "Anode_2") (pintype "passive"))
      (node (ref "R_Power") (pin "1") (pinfunction "1_1") (pintype "passive"))
    )
    (net (code "44") (name "unconnected-(U_SR-Q7-Pad9)") (class "Default")
      (node (ref "U_SR") (pin "9") (pinfunction "Q7_9") (pintype "output"))
    )
    (net (code "45") (name "unconnected-(X_In-Pad1)") (class "Default")
      (node (ref "X_In") (pin "1") (pinfunction "1_1") (pintype "passive"))
    )
    (net (code "46") (name "unconnected-(X_Out-Pad8)") (class "Default")
      (node (ref "X_Out") (pin "8") (pinfunction "8_8") (pintype "passive"))
    )
  )
)
